# MAIN_BOARD_01.net
KiCad netlist of a schematic drawn in EAGLE
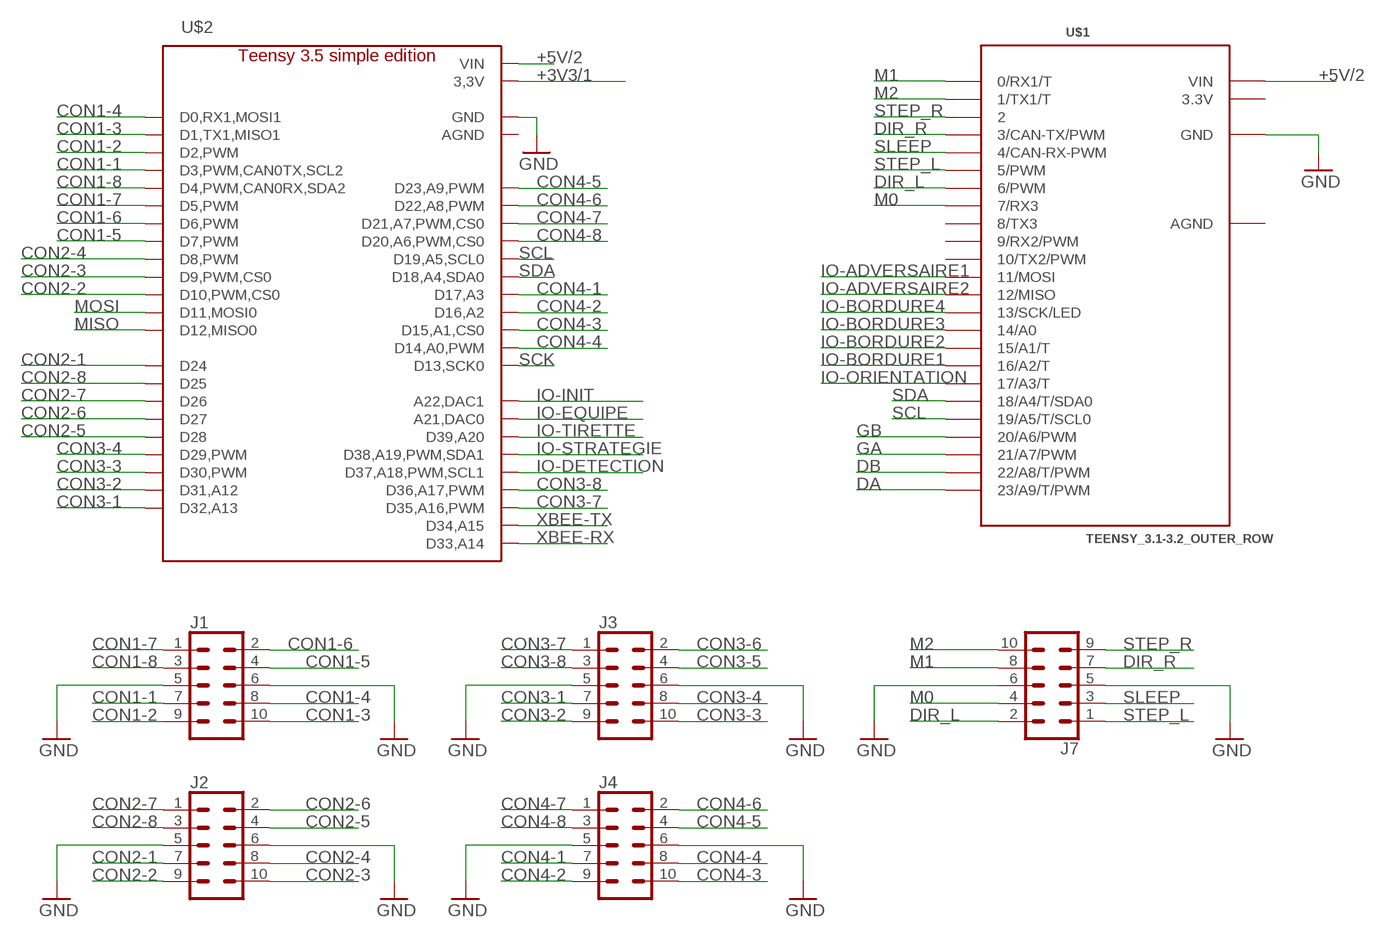
[diagram p0: schematic, sheet 1]
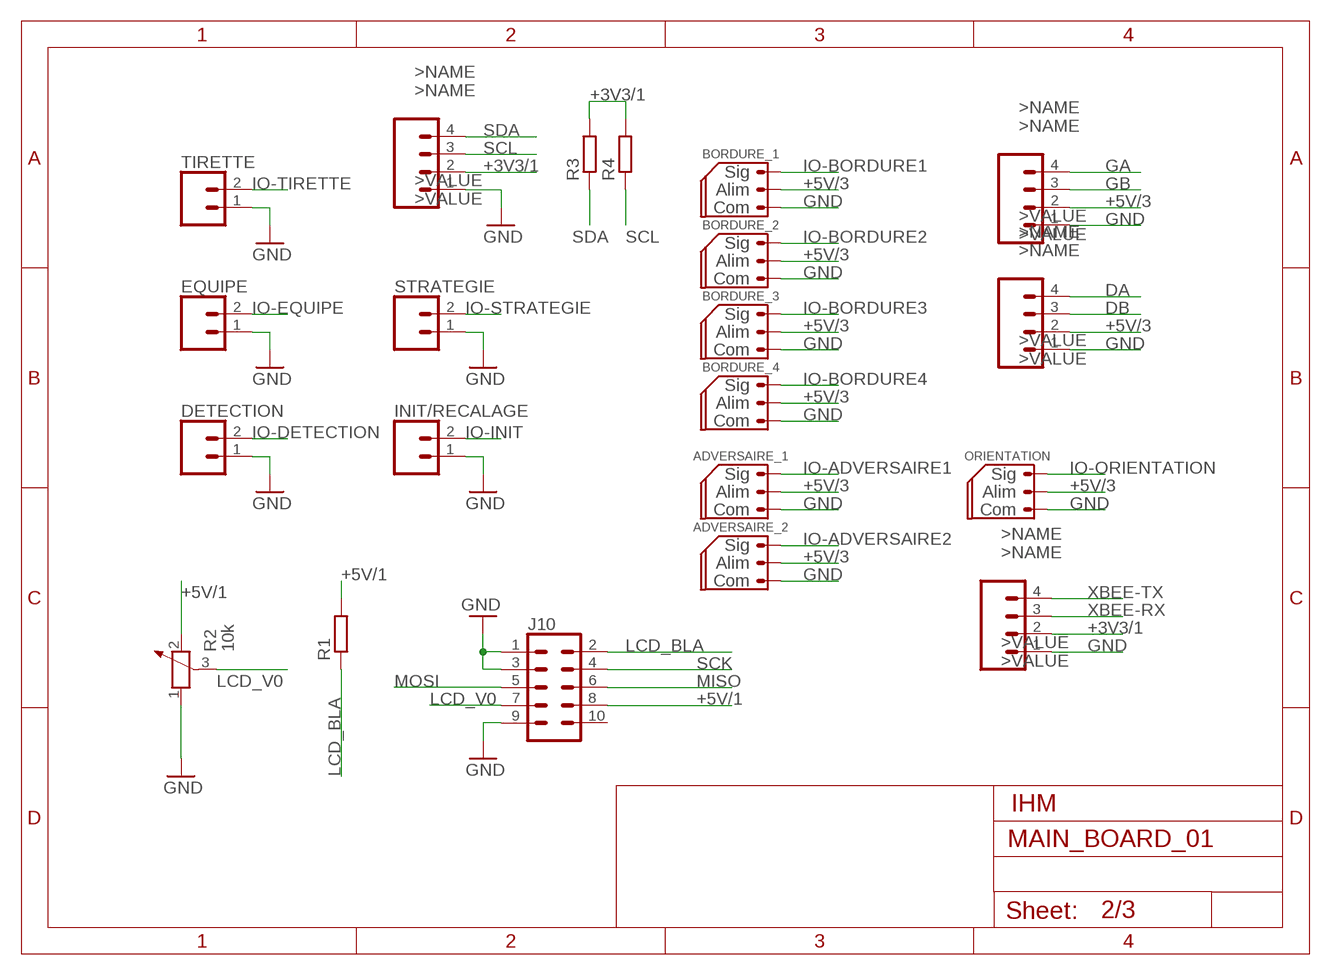
[diagram p1: schematic, sheet 2]
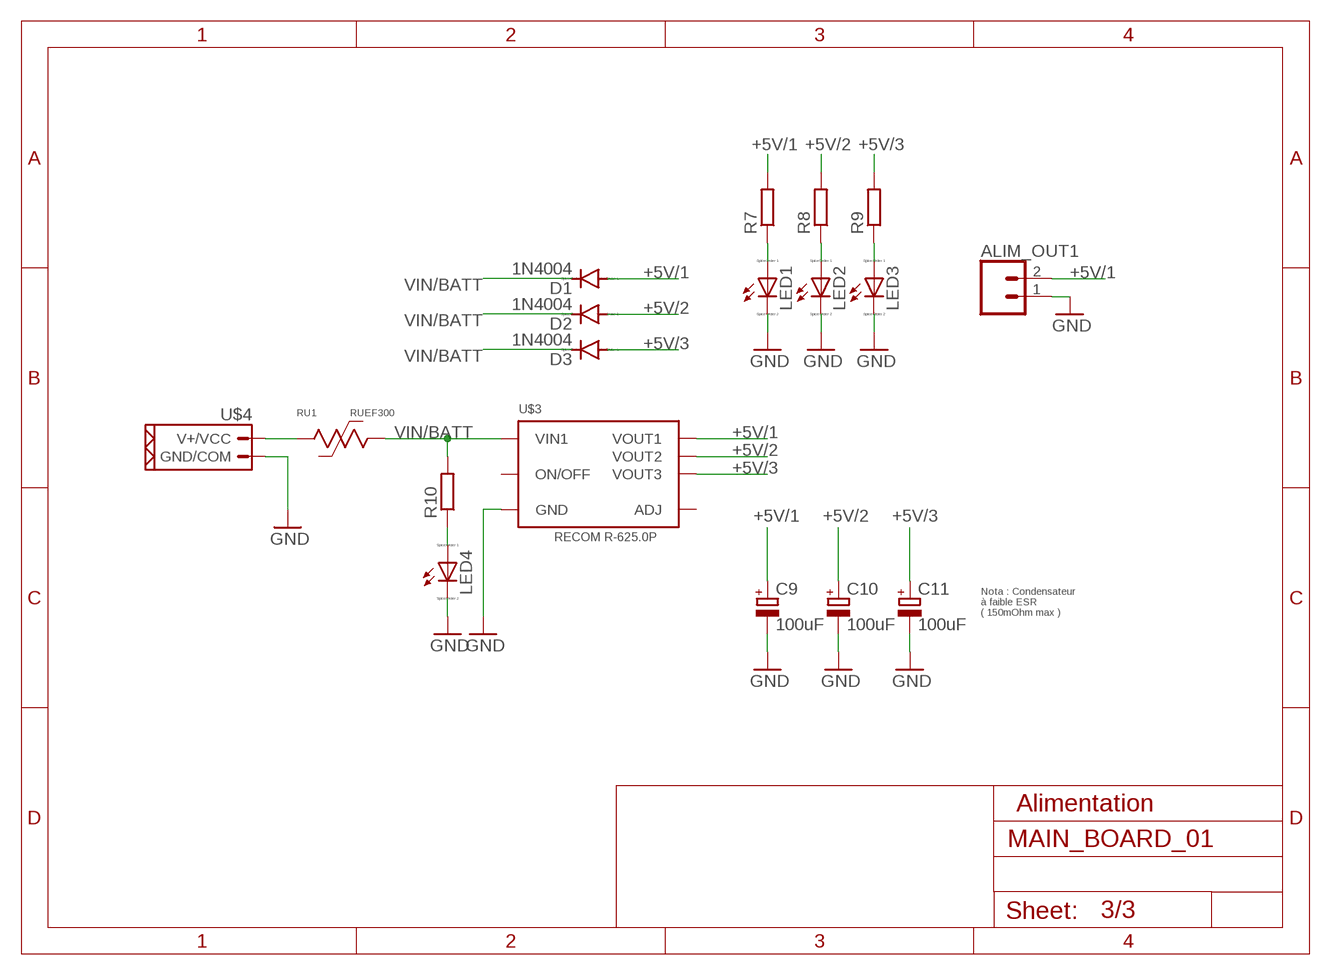
[diagram p2: schematic, sheet 3]

(export (version "E")
  (design (tool "Eeschema 10.0.6"))
  (components
    (comp (ref "ADVERSAIRE_1")
      (value "CONN_03_SERVO")
      (footprint "eagle-import:MOLEX-1X3")
      (libsource (lib "eagle-import") (part "CONN_03_SERVO"))
    )
    (comp (ref "ADVERSAIRE_2")
      (value "CONN_03_SERVO")
      (footprint "eagle-import:MOLEX-1X3")
      (libsource (lib "eagle-import") (part "CONN_03_SERVO"))
    )
    (comp (ref "BORDURE_1")
      (value "CONN_03_SERVO")
      (footprint "eagle-import:MOLEX-1X3")
      (libsource (lib "eagle-import") (part "CONN_03_SERVO"))
    )
    (comp (ref "BORDURE_2")
      (value "CONN_03_SERVO")
      (footprint "eagle-import:MOLEX-1X3")
      (libsource (lib "eagle-import") (part "CONN_03_SERVO"))
    )
    (comp (ref "BORDURE_3")
      (value "CONN_03_SERVO")
      (footprint "eagle-import:MOLEX-1X3")
      (libsource (lib "eagle-import") (part "CONN_03_SERVO"))
    )
    (comp (ref "BORDURE_4")
      (value "CONN_03_SERVO")
      (footprint "eagle-import:MOLEX-1X3")
      (libsource (lib "eagle-import") (part "CONN_03_SERVO"))
    )
    (comp (ref "COM-I2C")
      (value "CONN_04POLAR")
      (footprint "eagle-import:MOLEX-1X4")
      (libsource (lib "eagle-import") (part "CONN_04POLAR"))
    )
    (comp (ref "COM-XBEE")
      (value "CONN_04POLAR")
      (footprint "eagle-import:MOLEX-1X4")
      (libsource (lib "eagle-import") (part "CONN_04POLAR"))
    )
    (comp (ref "DETECTION")
      (value "CONN_02POLAR")
      (footprint "eagle-import:MOLEX-1X2")
      (libsource (lib "eagle-import") (part "CONN_02POLAR"))
    )
    (comp (ref "ENC_DROIT")
      (value "CONN_04POLAR")
      (footprint "eagle-import:MOLEX-1X4")
      (libsource (lib "eagle-import") (part "CONN_04POLAR"))
    )
    (comp (ref "ENC_GAUCHE")
      (value "CONN_04POLAR")
      (footprint "eagle-import:MOLEX-1X4")
      (libsource (lib "eagle-import") (part "CONN_04POLAR"))
    )
    (comp (ref "EQUIPE")
      (value "CONN_02POLAR")
      (footprint "eagle-import:MOLEX-1X2")
      (libsource (lib "eagle-import") (part "CONN_02POLAR"))
    )
    (comp (ref "INIT/RECALAGE")
      (value "CONN_02POLAR")
      (footprint "eagle-import:MOLEX-1X2")
      (libsource (lib "eagle-import") (part "CONN_02POLAR"))
    )
    (comp (ref "J10")
      (value "CONN_05X2SHD")
      (footprint "eagle-import:2X5-SHROUDED")
      (libsource (lib "eagle-import") (part "CONN_05X2SHD"))
    )
    (comp (ref "ORIENTATION")
      (value "CONN_03_SERVO")
      (footprint "eagle-import:MOLEX-1X3")
      (libsource (lib "eagle-import") (part "CONN_03_SERVO"))
    )
    (comp (ref "R1")
      (value "R-EU_R1206")
      (footprint "eagle-import:R1206")
      (libsource (lib "eagle-import") (part "R-EU_R1206"))
    )
    (comp (ref "R2")
      (value "10k")
      (footprint "eagle-import:PT-10")
      (libsource (lib "eagle-import") (part "POTENTIOMETER_PT-10"))
    )
    (comp (ref "R3")
      (value "R-EU_R1206")
      (footprint "eagle-import:R1206")
      (libsource (lib "eagle-import") (part "R-EU_R1206"))
    )
    (comp (ref "R4")
      (value "R-EU_R1206")
      (footprint "eagle-import:R1206")
      (libsource (lib "eagle-import") (part "R-EU_R1206"))
    )
    (comp (ref "STRATEGIE")
      (value "CONN_02POLAR")
      (footprint "eagle-import:MOLEX-1X2")
      (libsource (lib "eagle-import") (part "CONN_02POLAR"))
    )
    (comp (ref "TIRETTE")
      (value "CONN_02POLAR")
      (footprint "eagle-import:MOLEX-1X2")
      (libsource (lib "eagle-import") (part "CONN_02POLAR"))
    )
    (comp (ref "ALIM_OUT1")
      (value "CONN_02POLAR")
      (footprint "eagle-import:MOLEX-1X2")
      (libsource (lib "eagle-import") (part "CONN_02POLAR"))
    )
    (comp (ref "C9")
      (value "100uF")
      (footprint "eagle-import:E5-10,5")
      (libsource (lib "eagle-import") (part "CPOL-EUE5-10.5"))
    )
    (comp (ref "C10")
      (value "100uF")
      (footprint "eagle-import:E5-10,5")
      (libsource (lib "eagle-import") (part "CPOL-EUE5-10.5"))
    )
    (comp (ref "C11")
      (value "100uF")
      (footprint "eagle-import:E5-10,5")
      (libsource (lib "eagle-import") (part "CPOL-EUE5-10.5"))
    )
    (comp (ref "D1")
      (value "1N4004")
      (footprint "eagle-import:DO41-10")
      (libsource (lib "eagle-import") (part "1N4004"))
    )
    (comp (ref "D2")
      (value "1N4004")
      (footprint "eagle-import:DO41-10")
      (libsource (lib "eagle-import") (part "1N4004"))
    )
    (comp (ref "D3")
      (value "1N4004")
      (footprint "eagle-import:DO41-10")
      (libsource (lib "eagle-import") (part "1N4004"))
    )
    (comp (ref "LED1")
      (value "LED_E")
      (footprint "eagle-import:LED_1206")
      (libsource (lib "eagle-import") (part "LED_E"))
    )
    (comp (ref "LED2")
      (value "LED_E")
      (footprint "eagle-import:LED_1206")
      (libsource (lib "eagle-import") (part "LED_E"))
    )
    (comp (ref "LED3")
      (value "LED_E")
      (footprint "eagle-import:LED_1206")
      (libsource (lib "eagle-import") (part "LED_E"))
    )
    (comp (ref "LED4")
      (value "LED_E")
      (footprint "eagle-import:LED_1206")
      (libsource (lib "eagle-import") (part "LED_E"))
    )
    (comp (ref "R7")
      (value "R-EU_R1206")
      (footprint "eagle-import:R1206")
      (libsource (lib "eagle-import") (part "R-EU_R1206"))
    )
    (comp (ref "R8")
      (value "R-EU_R1206")
      (footprint "eagle-import:R1206")
      (libsource (lib "eagle-import") (part "R-EU_R1206"))
    )
    (comp (ref "R9")
      (value "R-EU_R1206")
      (footprint "eagle-import:R1206")
      (libsource (lib "eagle-import") (part "R-EU_R1206"))
    )
    (comp (ref "R10")
      (value "R-EU_R1206")
      (footprint "eagle-import:R1206")
      (libsource (lib "eagle-import") (part "R-EU_R1206"))
    )
    (comp (ref "RU1")
      (value "RUEF300")
      (footprint "eagle-import:RUEF300")
      (libsource (lib "eagle-import") (part "RUEF300"))
    )
    (comp (ref "U$3")
      (value "R-625.0P")
      (footprint "eagle-import:R-6XXXP")
      (libsource (lib "eagle-import") (part "R-625.0P"))
    )
    (comp (ref "U$4")
      (value "CONN_02_PUI")
      (footprint "eagle-import:NSK396-2C")
      (libsource (lib "eagle-import") (part "CONN_02_PUI"))
    )
    (comp (ref "J1")
      (value "CONN_05X2SHD")
      (footprint "eagle-import:2X5-SHROUDED")
      (libsource (lib "eagle-import") (part "CONN_05X2SHD"))
    )
    (comp (ref "J2")
      (value "CONN_05X2SHD")
      (footprint "eagle-import:2X5-SHROUDED")
      (libsource (lib "eagle-import") (part "CONN_05X2SHD"))
    )
    (comp (ref "J3")
      (value "CONN_05X2SHD")
      (footprint "eagle-import:2X5-SHROUDED")
      (libsource (lib "eagle-import") (part "CONN_05X2SHD"))
    )
    (comp (ref "J4")
      (value "CONN_05X2SHD")
      (footprint "eagle-import:2X5-SHROUDED")
      (libsource (lib "eagle-import") (part "CONN_05X2SHD"))
    )
    (comp (ref "J7")
      (value "CONN_05X2SHD")
      (footprint "eagle-import:2X5-SHROUDED")
      (libsource (lib "eagle-import") (part "CONN_05X2SHD"))
    )
    (comp (ref "U$1")
      (value "TEENSY_3.1-3.2_OUTER_ROW")
      (footprint "eagle-import:TEENSY_3.0-3.2&LC_OUTER_ROW")
      (libsource (lib "eagle-import") (part "TEENSY_3.1-3.2_OUTER_ROW"))
    )
    (comp (ref "U$2")
      (value "TEENSY_3.5")
      (footprint "eagle-import:TEENSY_3.5_LIGHT")
      (libsource (lib "eagle-import") (part "TEENSY_3.5"))
    )
  )
  (nets
    (net (code "1") (name "+3V3{slash}1") (class "Default")
      (node (ref "COM-I2C") (pin "2") (pinfunction "2_2") (pintype "passive"))
      (node (ref "COM-XBEE") (pin "2") (pinfunction "2_2") (pintype "passive"))
      (node (ref "R3") (pin "2") (pinfunction "2_2") (pintype "passive"))
      (node (ref "R4") (pin "2") (pinfunction "2_2") (pintype "passive"))
      (node (ref "U$2") (pin "P$15") (pinfunction "3,3V_P$15") (pintype "power_in"))
      (node (ref "U$2") (pin "P$46") (pinfunction "3,3V_P$46") (pintype "power_in"))
    )
    (net (code "2") (name "+5V{slash}1") (class "Default")
      (node (ref "ALIM_OUT1") (pin "2") (pinfunction "2_2") (pintype "passive"))
      (node (ref "C9") (pin "+") (pinfunction "+_+") (pintype "passive"))
      (node (ref "D1") (pin "A") (pinfunction "A_A") (pintype "passive"))
      (node (ref "J10") (pin "8") (pinfunction "8_8") (pintype "passive"))
      (node (ref "R1") (pin "2") (pinfunction "2_2") (pintype "passive"))
      (node (ref "R2") (pin "2") (pinfunction "2_2") (pintype "passive"))
      (node (ref "R7") (pin "2") (pinfunction "2_2") (pintype "passive"))
      (node (ref "U$3") (pin "P$9") (pinfunction "VOUT1_P$9") (pintype "power_in"))
    )
    (net (code "3") (name "+5V{slash}2") (class "Default")
      (node (ref "C10") (pin "+") (pinfunction "+_+") (pintype "passive"))
      (node (ref "D2") (pin "A") (pinfunction "A_A") (pintype "passive"))
      (node (ref "R8") (pin "2") (pinfunction "2_2") (pintype "passive"))
      (node (ref "U$1") (pin "V_IN") (pinfunction "VIN_V_IN") (pintype "power_in"))
      (node (ref "U$2") (pin "P$48") (pinfunction "VIN_P$48") (pintype "passive"))
      (node (ref "U$3") (pin "P$10") (pinfunction "VOUT2_P$10") (pintype "power_in"))
    )
    (net (code "4") (name "+5V{slash}3") (class "Default")
      (node (ref "ADVERSAIRE_1") (pin "2") (pinfunction "2_2") (pintype "passive"))
      (node (ref "ADVERSAIRE_2") (pin "2") (pinfunction "2_2") (pintype "passive"))
      (node (ref "BORDURE_1") (pin "2") (pinfunction "2_2") (pintype "passive"))
      (node (ref "BORDURE_2") (pin "2") (pinfunction "2_2") (pintype "passive"))
      (node (ref "BORDURE_3") (pin "2") (pinfunction "2_2") (pintype "passive"))
      (node (ref "BORDURE_4") (pin "2") (pinfunction "2_2") (pintype "passive"))
      (node (ref "C11") (pin "+") (pinfunction "+_+") (pintype "passive"))
      (node (ref "D3") (pin "A") (pinfunction "A_A") (pintype "passive"))
      (node (ref "ENC_DROIT") (pin "2") (pinfunction "2_2") (pintype "passive"))
      (node (ref "ENC_GAUCHE") (pin "2") (pinfunction "2_2") (pintype "passive"))
      (node (ref "ORIENTATION") (pin "2") (pinfunction "2_2") (pintype "passive"))
      (node (ref "R9") (pin "2") (pinfunction "2_2") (pintype "passive"))
      (node (ref "U$3") (pin "P$11") (pinfunction "VOUT3_P$11") (pintype "power_in"))
    )
    (net (code "5") (name "3.3V") (class "Default")
      (node (ref "U$1") (pin "3.3V") (pinfunction "3.3V_3.3V") (pintype "power_in"))
    )
    (net (code "6") (name "ADJ") (class "Default")
      (node (ref "U$3") (pin "P$12") (pinfunction "ADJ_P$12") (pintype "power_in"))
    )
    (net (code "7") (name "AGND") (class "Default")
      (node (ref "U$1") (pin "AGND") (pinfunction "AGND_AGND") (pintype "power_in"))
    )
    (net (code "8") (name "CON1-1") (class "Default")
      (node (ref "J1") (pin "7") (pinfunction "7_7") (pintype "passive"))
      (node (ref "U$2") (pin "P$5") (pinfunction "D3,PWM,CAN0TX,SCL2_P$5") (pintype "passive"))
    )
    (net (code "9") (name "CON1-2") (class "Default")
      (node (ref "J1") (pin "9") (pinfunction "9_9") (pintype "passive"))
      (node (ref "U$2") (pin "P$4") (pinfunction "D2,PWM_P$4") (pintype "passive"))
    )
    (net (code "10") (name "CON1-3") (class "Default")
      (node (ref "J1") (pin "10") (pinfunction "10_10") (pintype "passive"))
      (node (ref "U$2") (pin "P$3") (pinfunction "D1,TX1,MISO1_P$3") (pintype "passive"))
    )
    (net (code "11") (name "CON1-4") (class "Default")
      (node (ref "J1") (pin "8") (pinfunction "8_8") (pintype "passive"))
      (node (ref "U$2") (pin "P$2") (pinfunction "D0,RX1,MOSI1_P$2") (pintype "passive"))
    )
    (net (code "12") (name "CON1-5") (class "Default")
      (node (ref "J1") (pin "4") (pinfunction "4_4") (pintype "passive"))
      (node (ref "U$2") (pin "P$9") (pinfunction "D7,PWM_P$9") (pintype "passive"))
    )
    (net (code "13") (name "CON1-6") (class "Default")
      (node (ref "J1") (pin "2") (pinfunction "2_2") (pintype "passive"))
      (node (ref "U$2") (pin "P$8") (pinfunction "D6,PWM_P$8") (pintype "passive"))
    )
    (net (code "14") (name "CON1-7") (class "Default")
      (node (ref "J1") (pin "1") (pinfunction "1_1") (pintype "passive"))
      (node (ref "U$2") (pin "P$7") (pinfunction "D5,PWM_P$7") (pintype "passive"))
    )
    (net (code "15") (name "CON1-8") (class "Default")
      (node (ref "J1") (pin "3") (pinfunction "3_3") (pintype "passive"))
      (node (ref "U$2") (pin "P$6") (pinfunction "D4,PWM,CAN0RX,SDA2_P$6") (pintype "passive"))
    )
    (net (code "16") (name "CON2-1") (class "Default")
      (node (ref "J2") (pin "7") (pinfunction "7_7") (pintype "passive"))
      (node (ref "U$2") (pin "P$16") (pinfunction "D24_P$16") (pintype "passive"))
    )
    (net (code "17") (name "CON2-2") (class "Default")
      (node (ref "J2") (pin "9") (pinfunction "9_9") (pintype "passive"))
      (node (ref "U$2") (pin "P$12") (pinfunction "D10,PWM,CS0_P$12") (pintype "passive"))
    )
    (net (code "18") (name "CON2-3") (class "Default")
      (node (ref "J2") (pin "10") (pinfunction "10_10") (pintype "passive"))
      (node (ref "U$2") (pin "P$11") (pinfunction "D9,PWM,CS0_P$11") (pintype "passive"))
    )
    (net (code "19") (name "CON2-4") (class "Default")
      (node (ref "J2") (pin "8") (pinfunction "8_8") (pintype "passive"))
      (node (ref "U$2") (pin "P$10") (pinfunction "D8,PWM_P$10") (pintype "passive"))
    )
    (net (code "20") (name "CON2-5") (class "Default")
      (node (ref "J2") (pin "4") (pinfunction "4_4") (pintype "passive"))
      (node (ref "U$2") (pin "P$20") (pinfunction "D28_P$20") (pintype "passive"))
    )
    (net (code "21") (name "CON2-6") (class "Default")
      (node (ref "J2") (pin "2") (pinfunction "2_2") (pintype "passive"))
      (node (ref "U$2") (pin "P$19") (pinfunction "D27_P$19") (pintype "passive"))
    )
    (net (code "22") (name "CON2-7") (class "Default")
      (node (ref "J2") (pin "1") (pinfunction "1_1") (pintype "passive"))
      (node (ref "U$2") (pin "P$18") (pinfunction "D26_P$18") (pintype "passive"))
    )
    (net (code "23") (name "CON2-8") (class "Default")
      (node (ref "J2") (pin "3") (pinfunction "3_3") (pintype "passive"))
      (node (ref "U$2") (pin "P$17") (pinfunction "D25_P$17") (pintype "passive"))
    )
    (net (code "24") (name "CON3-1") (class "Default")
      (node (ref "J3") (pin "7") (pinfunction "7_7") (pintype "passive"))
      (node (ref "U$2") (pin "P$24") (pinfunction "D32,A13_P$24") (pintype "passive"))
    )
    (net (code "25") (name "CON3-2") (class "Default")
      (node (ref "J3") (pin "9") (pinfunction "9_9") (pintype "passive"))
      (node (ref "U$2") (pin "P$23") (pinfunction "D31,A12_P$23") (pintype "passive"))
    )
    (net (code "26") (name "CON3-3") (class "Default")
      (node (ref "J3") (pin "10") (pinfunction "10_10") (pintype "passive"))
      (node (ref "U$2") (pin "P$22") (pinfunction "D30,PWM_P$22") (pintype "passive"))
    )
    (net (code "27") (name "CON3-4") (class "Default")
      (node (ref "J3") (pin "8") (pinfunction "8_8") (pintype "passive"))
      (node (ref "U$2") (pin "P$21") (pinfunction "D29,PWM_P$21") (pintype "passive"))
    )
    (net (code "28") (name "CON3-5") (class "Default")
      (node (ref "J3") (pin "4") (pinfunction "4_4") (pintype "passive"))
    )
    (net (code "29") (name "CON3-6") (class "Default")
      (node (ref "J3") (pin "2") (pinfunction "2_2") (pintype "passive"))
    )
    (net (code "30") (name "CON3-7") (class "Default")
      (node (ref "J3") (pin "1") (pinfunction "1_1") (pintype "passive"))
      (node (ref "U$2") (pin "P$27") (pinfunction "D35,A16,PWM_P$27") (pintype "passive"))
    )
    (net (code "31") (name "CON3-8") (class "Default")
      (node (ref "J3") (pin "3") (pinfunction "3_3") (pintype "passive"))
      (node (ref "U$2") (pin "P$28") (pinfunction "D36,A17,PWM_P$28") (pintype "passive"))
    )
    (net (code "32") (name "CON4-1") (class "Default")
      (node (ref "J4") (pin "7") (pinfunction "7_7") (pintype "passive"))
      (node (ref "U$2") (pin "P$39") (pinfunction "D17,A3_P$39") (pintype "passive"))
    )
    (net (code "33") (name "CON4-2") (class "Default")
      (node (ref "J4") (pin "9") (pinfunction "9_9") (pintype "passive"))
      (node (ref "U$2") (pin "P$38") (pinfunction "D16,A2_P$38") (pintype "passive"))
    )
    (net (code "34") (name "CON4-3") (class "Default")
      (node (ref "J4") (pin "10") (pinfunction "10_10") (pintype "passive"))
      (node (ref "U$2") (pin "P$37") (pinfunction "D15,A1,CS0_P$37") (pintype "passive"))
    )
    (net (code "35") (name "CON4-4") (class "Default")
      (node (ref "J4") (pin "8") (pinfunction "8_8") (pintype "passive"))
      (node (ref "U$2") (pin "P$36") (pinfunction "D14,A0,PWM_P$36") (pintype "passive"))
    )
    (net (code "36") (name "CON4-5") (class "Default")
      (node (ref "J4") (pin "4") (pinfunction "4_4") (pintype "passive"))
      (node (ref "U$2") (pin "P$45") (pinfunction "D23,A9,PWM_P$45") (pintype "passive"))
    )
    (net (code "37") (name "CON4-6") (class "Default")
      (node (ref "J4") (pin "2") (pinfunction "2_2") (pintype "passive"))
      (node (ref "U$2") (pin "P$44") (pinfunction "D22,A8,PWM_P$44") (pintype "passive"))
    )
    (net (code "38") (name "CON4-7") (class "Default")
      (node (ref "J4") (pin "1") (pinfunction "1_1") (pintype "passive"))
      (node (ref "U$2") (pin "P$43") (pinfunction "D21,A7,PWM,CS0_P$43") (pintype "passive"))
    )
    (net (code "39") (name "CON4-8") (class "Default")
      (node (ref "J4") (pin "3") (pinfunction "3_3") (pintype "passive"))
      (node (ref "U$2") (pin "P$42") (pinfunction "D20,A6,PWM,CS0_P$42") (pintype "passive"))
    )
    (net (code "40") (name "DA") (class "Default")
      (node (ref "ENC_DROIT") (pin "4") (pinfunction "4_4") (pintype "passive"))
      (node (ref "U$1") (pin "23/A9") (pinfunction "23/A9/T/PWM_23/A9") (pintype "bidirectional"))
    )
    (net (code "41") (name "DB") (class "Default")
      (node (ref "ENC_DROIT") (pin "3") (pinfunction "3_3") (pintype "passive"))
      (node (ref "U$1") (pin "22/A8") (pinfunction "22/A8/T/PWM_22/A8") (pintype "bidirectional"))
    )
    (net (code "42") (name "DIR_L") (class "Default")
      (node (ref "J7") (pin "2") (pinfunction "2_2") (pintype "passive"))
      (node (ref "U$1") (pin "6") (pinfunction "6/PWM_6") (pintype "bidirectional"))
    )
    (net (code "43") (name "DIR_R") (class "Default")
      (node (ref "J7") (pin "7") (pinfunction "7_7") (pintype "passive"))
      (node (ref "U$1") (pin "3") (pinfunction "3/CAN-TX/PWM_3") (pintype "bidirectional"))
    )
    (net (code "44") (name "GA") (class "Default")
      (node (ref "ENC_GAUCHE") (pin "4") (pinfunction "4_4") (pintype "passive"))
      (node (ref "U$1") (pin "21/A7") (pinfunction "21/A7/PWM_21/A7") (pintype "bidirectional"))
    )
    (net (code "45") (name "GB") (class "Default")
      (node (ref "ENC_GAUCHE") (pin "3") (pinfunction "3_3") (pintype "passive"))
      (node (ref "U$1") (pin "20/A6") (pinfunction "20/A6/PWM_20/A6") (pintype "bidirectional"))
    )
    (net (code "46") (name "GND") (class "Default")
      (node (ref "ADVERSAIRE_1") (pin "1") (pinfunction "1_1") (pintype "passive"))
      (node (ref "ADVERSAIRE_2") (pin "1") (pinfunction "1_1") (pintype "passive"))
      (node (ref "ALIM_OUT1") (pin "1") (pinfunction "1_1") (pintype "passive"))
      (node (ref "BORDURE_1") (pin "1") (pinfunction "1_1") (pintype "passive"))
      (node (ref "BORDURE_2") (pin "1") (pinfunction "1_1") (pintype "passive"))
      (node (ref "BORDURE_3") (pin "1") (pinfunction "1_1") (pintype "passive"))
      (node (ref "BORDURE_4") (pin "1") (pinfunction "1_1") (pintype "passive"))
      (node (ref "C10") (pin "-") (pinfunction "-_-") (pintype "passive"))
      (node (ref "C11") (pin "-") (pinfunction "-_-") (pintype "passive"))
      (node (ref "C9") (pin "-") (pinfunction "-_-") (pintype "passive"))
      (node (ref "COM-I2C") (pin "1") (pinfunction "1_1") (pintype "passive"))
      (node (ref "COM-XBEE") (pin "1") (pinfunction "1_1") (pintype "passive"))
      (node (ref "DETECTION") (pin "1") (pinfunction "1_1") (pintype "passive"))
      (node (ref "ENC_DROIT") (pin "1") (pinfunction "1_1") (pintype "passive"))
      (node (ref "ENC_GAUCHE") (pin "1") (pinfunction "1_1") (pintype "passive"))
      (node (ref "EQUIPE") (pin "1") (pinfunction "1_1") (pintype "passive"))
      (node (ref "INIT/RECALAGE") (pin "1") (pinfunction "1_1") (pintype "passive"))
      (node (ref "J1") (pin "5") (pinfunction "5_5") (pintype "passive"))
      (node (ref "J1") (pin "6") (pinfunction "6_6") (pintype "passive"))
      (node (ref "J10") (pin "1") (pinfunction "1_1") (pintype "passive"))
      (node (ref "J10") (pin "3") (pinfunction "3_3") (pintype "passive"))
      (node (ref "J10") (pin "9") (pinfunction "9_9") (pintype "passive"))
      (node (ref "J2") (pin "5") (pinfunction "5_5") (pintype "passive"))
      (node (ref "J2") (pin "6") (pinfunction "6_6") (pintype "passive"))
      (node (ref "J3") (pin "5") (pinfunction "5_5") (pintype "passive"))
      (node (ref "J3") (pin "6") (pinfunction "6_6") (pintype "passive"))
      (node (ref "J4") (pin "5") (pinfunction "5_5") (pintype "passive"))
      (node (ref "J4") (pin "6") (pinfunction "6_6") (pintype "passive"))
      (node (ref "J7") (pin "5") (pinfunction "5_5") (pintype "passive"))
      (node (ref "J7") (pin "6") (pinfunction "6_6") (pintype "passive"))
      (node (ref "LED1") (pin "C") (pinfunction "C_C") (pintype "passive"))
      (node (ref "LED2") (pin "C") (pinfunction "C_C") (pintype "passive"))
      (node (ref "LED3") (pin "C") (pinfunction "C_C") (pintype "passive"))
      (node (ref "LED4") (pin "C") (pinfunction "C_C") (pintype "passive"))
      (node (ref "ORIENTATION") (pin "1") (pinfunction "1_1") (pintype "passive"))
      (node (ref "R2") (pin "1") (pinfunction "1_1") (pintype "passive"))
      (node (ref "STRATEGIE") (pin "1") (pinfunction "1_1") (pintype "passive"))
      (node (ref "TIRETTE") (pin "1") (pinfunction "1_1") (pintype "passive"))
      (node (ref "U$1") (pin "GND") (pinfunction "GND_GND") (pintype "power_in"))
      (node (ref "U$2") (pin "GND") (pinfunction "GND_GND") (pintype "power_in"))
      (node (ref "U$2") (pin "P$34") (pinfunction "GND_P$34") (pintype "power_in"))
      (node (ref "U$3") (pin "P$5") (pinfunction "GND_P$5") (pintype "power_in"))
      (node (ref "U$3") (pin "P$6") (pinfunction "GND_P$6") (pintype "power_in"))
      (node (ref "U$3") (pin "P$7") (pinfunction "GND_P$7") (pintype "power_in"))
      (node (ref "U$3") (pin "P$8") (pinfunction "GND_P$8") (pintype "power_in"))
      (node (ref "U$4") (pin "P$1") (pinfunction "GND/COM_P$1") (pintype "passive"))
    )
    (net (code "47") (name "IO-ADVERSAIRE1") (class "Default")
      (node (ref "ADVERSAIRE_1") (pin "3") (pinfunction "3_3") (pintype "passive"))
      (node (ref "U$1") (pin "11") (pinfunction "11/MOSI_11") (pintype "bidirectional"))
    )
    (net (code "48") (name "IO-ADVERSAIRE2") (class "Default")
      (node (ref "ADVERSAIRE_2") (pin "3") (pinfunction "3_3") (pintype "passive"))
      (node (ref "U$1") (pin "12") (pinfunction "12/MISO_12") (pintype "bidirectional"))
    )
    (net (code "49") (name "IO-BORDURE1") (class "Default")
      (node (ref "BORDURE_1") (pin "3") (pinfunction "3_3") (pintype "passive"))
      (node (ref "U$1") (pin "16/A2") (pinfunction "16/A2/T_16/A2") (pintype "bidirectional"))
    )
    (net (code "50") (name "IO-BORDURE2") (class "Default")
      (node (ref "BORDURE_2") (pin "3") (pinfunction "3_3") (pintype "passive"))
      (node (ref "U$1") (pin "15/A1") (pinfunction "15/A1/T_15/A1") (pintype "bidirectional"))
    )
    (net (code "51") (name "IO-BORDURE3") (class "Default")
      (node (ref "BORDURE_3") (pin "3") (pinfunction "3_3") (pintype "passive"))
      (node (ref "U$1") (pin "14/A0") (pinfunction "14/A0_14/A0") (pintype "bidirectional"))
    )
    (net (code "52") (name "IO-BORDURE4") (class "Default")
      (node (ref "BORDURE_4") (pin "3") (pinfunction "3_3") (pintype "passive"))
      (node (ref "U$1") (pin "13") (pinfunction "13/SCK/LED_13") (pintype "bidirectional"))
    )
    (net (code "53") (name "IO-DETECTION") (class "Default")
      (node (ref "DETECTION") (pin "2") (pinfunction "2_2") (pintype "passive"))
      (node (ref "U$2") (pin "P$29") (pinfunction "D37,A18,PWM,SCL1_P$29") (pintype "passive"))
    )
    (net (code "54") (name "IO-EQUIPE") (class "Default")
      (node (ref "EQUIPE") (pin "2") (pinfunction "2_2") (pintype "passive"))
      (node (ref "U$2") (pin "P$32") (pinfunction "A21,DAC0_P$32") (pintype "passive"))
    )
    (net (code "55") (name "IO-INIT") (class "Default")
      (node (ref "INIT/RECALAGE") (pin "2") (pinfunction "2_2") (pintype "passive"))
      (node (ref "U$2") (pin "P$33") (pinfunction "A22,DAC1_P$33") (pintype "passive"))
    )
    (net (code "56") (name "IO-ORIENTATION") (class "Default")
      (node (ref "ORIENTATION") (pin "3") (pinfunction "3_3") (pintype "passive"))
      (node (ref "U$1") (pin "17/A3") (pinfunction "17/A3/T_17/A3") (pintype "bidirectional"))
    )
    (net (code "57") (name "IO-STRATEGIE") (class "Default")
      (node (ref "STRATEGIE") (pin "2") (pinfunction "2_2") (pintype "passive"))
      (node (ref "U$2") (pin "P$30") (pinfunction "D38,A19,PWM,SDA1_P$30") (pintype "passive"))
    )
    (net (code "58") (name "IO-TIRETTE") (class "Default")
      (node (ref "TIRETTE") (pin "2") (pinfunction "2_2") (pintype "passive"))
      (node (ref "U$2") (pin "P$31") (pinfunction "D39,A20_P$31") (pintype "passive"))
    )
    (net (code "59") (name "LCD_BLA") (class "Default")
      (node (ref "J10") (pin "2") (pinfunction "2_2") (pintype "passive"))
      (node (ref "R1") (pin "1") (pinfunction "1_1") (pintype "passive"))
    )
    (net (code "60") (name "LCD_V0") (class "Default")
      (node (ref "J10") (pin "7") (pinfunction "7_7") (pintype "passive"))
      (node (ref "R2") (pin "3") (pinfunction "3_3") (pintype "passive"))
    )
    (net (code "61") (name "M0") (class "Default")
      (node (ref "J7") (pin "4") (pinfunction "4_4") (pintype "passive"))
      (node (ref "U$1") (pin "7") (pinfunction "7/RX3_7") (pintype "bidirectional"))
    )
    (net (code "62") (name "M1") (class "Default")
      (node (ref "J7") (pin "8") (pinfunction "8_8") (pintype "passive"))
      (node (ref "U$1") (pin "0") (pinfunction "0/RX1/T_0") (pintype "bidirectional"))
    )
    (net (code "63") (name "M2") (class "Default")
      (node (ref "J7") (pin "10") (pinfunction "10_10") (pintype "passive"))
      (node (ref "U$1") (pin "1") (pinfunction "1/TX1/T_1") (pintype "bidirectional"))
    )
    (net (code "64") (name "MISO") (class "Default")
      (node (ref "J10") (pin "6") (pinfunction "6_6") (pintype "passive"))
      (node (ref "U$2") (pin "P$14") (pinfunction "D12,MISO0_P$14") (pintype "passive"))
    )
    (net (code "65") (name "MOSI") (class "Default")
      (node (ref "J10") (pin "5") (pinfunction "5_5") (pintype "passive"))
      (node (ref "U$2") (pin "P$13") (pinfunction "D11,MOSI0_P$13") (pintype "passive"))
    )
    (net (code "66") (name "Net-(LED1-PadA)") (class "Default")
      (node (ref "LED1") (pin "A") (pinfunction "A_A") (pintype "passive"))
      (node (ref "R7") (pin "1") (pinfunction "1_1") (pintype "passive"))
    )
    (net (code "67") (name "Net-(LED2-PadA)") (class "Default")
      (node (ref "LED2") (pin "A") (pinfunction "A_A") (pintype "passive"))
      (node (ref "R8") (pin "1") (pinfunction "1_1") (pintype "passive"))
    )
    (net (code "68") (name "Net-(LED3-PadA)") (class "Default")
      (node (ref "LED3") (pin "A") (pinfunction "A_A") (pintype "passive"))
      (node (ref "R9") (pin "1") (pinfunction "1_1") (pintype "passive"))
    )
    (net (code "69") (name "Net-(LED4-PadA)") (class "Default")
      (node (ref "LED4") (pin "A") (pinfunction "A_A") (pintype "passive"))
      (node (ref "R10") (pin "1") (pinfunction "1_1") (pintype "passive"))
    )
    (net (code "70") (name "Net-(U$4-V+{slash}VCC)") (class "Default")
      (node (ref "RU1") (pin "P$1") (pinfunction "P$1_P$1") (pintype "passive"))
      (node (ref "U$4") (pin "P$2") (pinfunction "V+/VCC_P$2") (pintype "passive"))
    )
    (net (code "71") (name "SCK") (class "Default")
      (node (ref "J10") (pin "4") (pinfunction "4_4") (pintype "passive"))
      (node (ref "U$2") (pin "P$35") (pinfunction "D13,SCK0_P$35") (pintype "passive"))
    )
    (net (code "72") (name "SCL") (class "Default")
      (node (ref "COM-I2C") (pin "3") (pinfunction "3_3") (pintype "passive"))
      (node (ref "R4") (pin "1") (pinfunction "1_1") (pintype "passive"))
      (node (ref "U$1") (pin "19/A5") (pinfunction "19/A5/T/SCL0_19/A5") (pintype "bidirectional"))
      (node (ref "U$2") (pin "P$41") (pinfunction "D19,A5,SCL0_P$41") (pintype "passive"))
    )
    (net (code "73") (name "SDA") (class "Default")
      (node (ref "COM-I2C") (pin "4") (pinfunction "4_4") (pintype "passive"))
      (node (ref "R3") (pin "1") (pinfunction "1_1") (pintype "passive"))
      (node (ref "U$1") (pin "18/A4") (pinfunction "18/A4/T/SDA0_18/A4") (pintype "bidirectional"))
      (node (ref "U$2") (pin "P$40") (pinfunction "D18,A4,SDA0_P$40") (pintype "passive"))
    )
    (net (code "74") (name "SLEEP") (class "Default")
      (node (ref "J7") (pin "3") (pinfunction "3_3") (pintype "passive"))
      (node (ref "U$1") (pin "4") (pinfunction "4/CAN-RX-PWM_4") (pintype "bidirectional"))
    )
    (net (code "75") (name "STEP_L") (class "Default")
      (node (ref "J7") (pin "1") (pinfunction "1_1") (pintype "passive"))
      (node (ref "U$1") (pin "5") (pinfunction "5/PWM_5") (pintype "bidirectional"))
    )
    (net (code "76") (name "STEP_R") (class "Default")
      (node (ref "J7") (pin "9") (pinfunction "9_9") (pintype "passive"))
      (node (ref "U$1") (pin "2") (pinfunction "2_2") (pintype "bidirectional"))
    )
    (net (code "77") (name "VIN{slash}BATT") (class "Default")
      (node (ref "D1") (pin "C") (pinfunction "C_C") (pintype "passive"))
      (node (ref "D2") (pin "C") (pinfunction "C_C") (pintype "passive"))
      (node (ref "D3") (pin "C") (pinfunction "C_C") (pintype "passive"))
      (node (ref "R10") (pin "2") (pinfunction "2_2") (pintype "passive"))
      (node (ref "RU1") (pin "P$2") (pinfunction "P$2_P$2") (pintype "passive"))
      (node (ref "U$3") (pin "P$2") (pinfunction "VIN1_P$2") (pintype "power_in"))
      (node (ref "U$3") (pin "P$3") (pinfunction "VIN1_P$3") (pintype "power_in"))
      (node (ref "U$3") (pin "P$4") (pinfunction "VIN1_P$4") (pintype "power_in"))
    )
    (net (code "78") (name "XBEE-RX") (class "Default")
      (node (ref "COM-XBEE") (pin "3") (pinfunction "3_3") (pintype "passive"))
      (node (ref "U$2") (pin "P$25") (pinfunction "D33,A14_P$25") (pintype "passive"))
    )
    (net (code "79") (name "XBEE-TX") (class "Default")
      (node (ref "COM-XBEE") (pin "4") (pinfunction "4_4") (pintype "passive"))
      (node (ref "U$2") (pin "P$26") (pinfunction "D34,A15_P$26") (pintype "passive"))
    )
    (net (code "80") (name "unconnected-(J10-Pad10)") (class "Default")
      (node (ref "J10") (pin "10") (pinfunction "10_10") (pintype "passive"))
    )
    (net (code "81") (name "unconnected-(U$1-8{slash}TX3-Pad8)") (class "Default")
      (node (ref "U$1") (pin "8") (pinfunction "8/TX3_8") (pintype "bidirectional"))
    )
    (net (code "82") (name "unconnected-(U$1-9{slash}RX2{slash}PWM-Pad9)") (class "Default")
      (node (ref "U$1") (pin "9") (pinfunction "9/RX2/PWM_9") (pintype "bidirectional"))
    )
    (net (code "83") (name "unconnected-(U$1-10{slash}TX2{slash}PWM-Pad10)") (class "Default")
      (node (ref "U$1") (pin "10") (pinfunction "10/TX2/PWM_10") (pintype "bidirectional"))
    )
    (net (code "84") (name "unconnected-(U$2-AGND-PadP$47)") (class "Default")
      (node (ref "U$2") (pin "P$47") (pinfunction "AGND_P$47") (pintype "passive"))
    )
    (net (code "85") (name "unconnected-(U$3-ON{slash}OFF-PadP$1)") (class "Default")
      (node (ref "U$3") (pin "P$1") (pinfunction "ON/OFF_P$1") (pintype "passive"))
    )
  )
)
